# Arduino_Board.net
KiCad netlist of a schematic drawn in Altium Designer
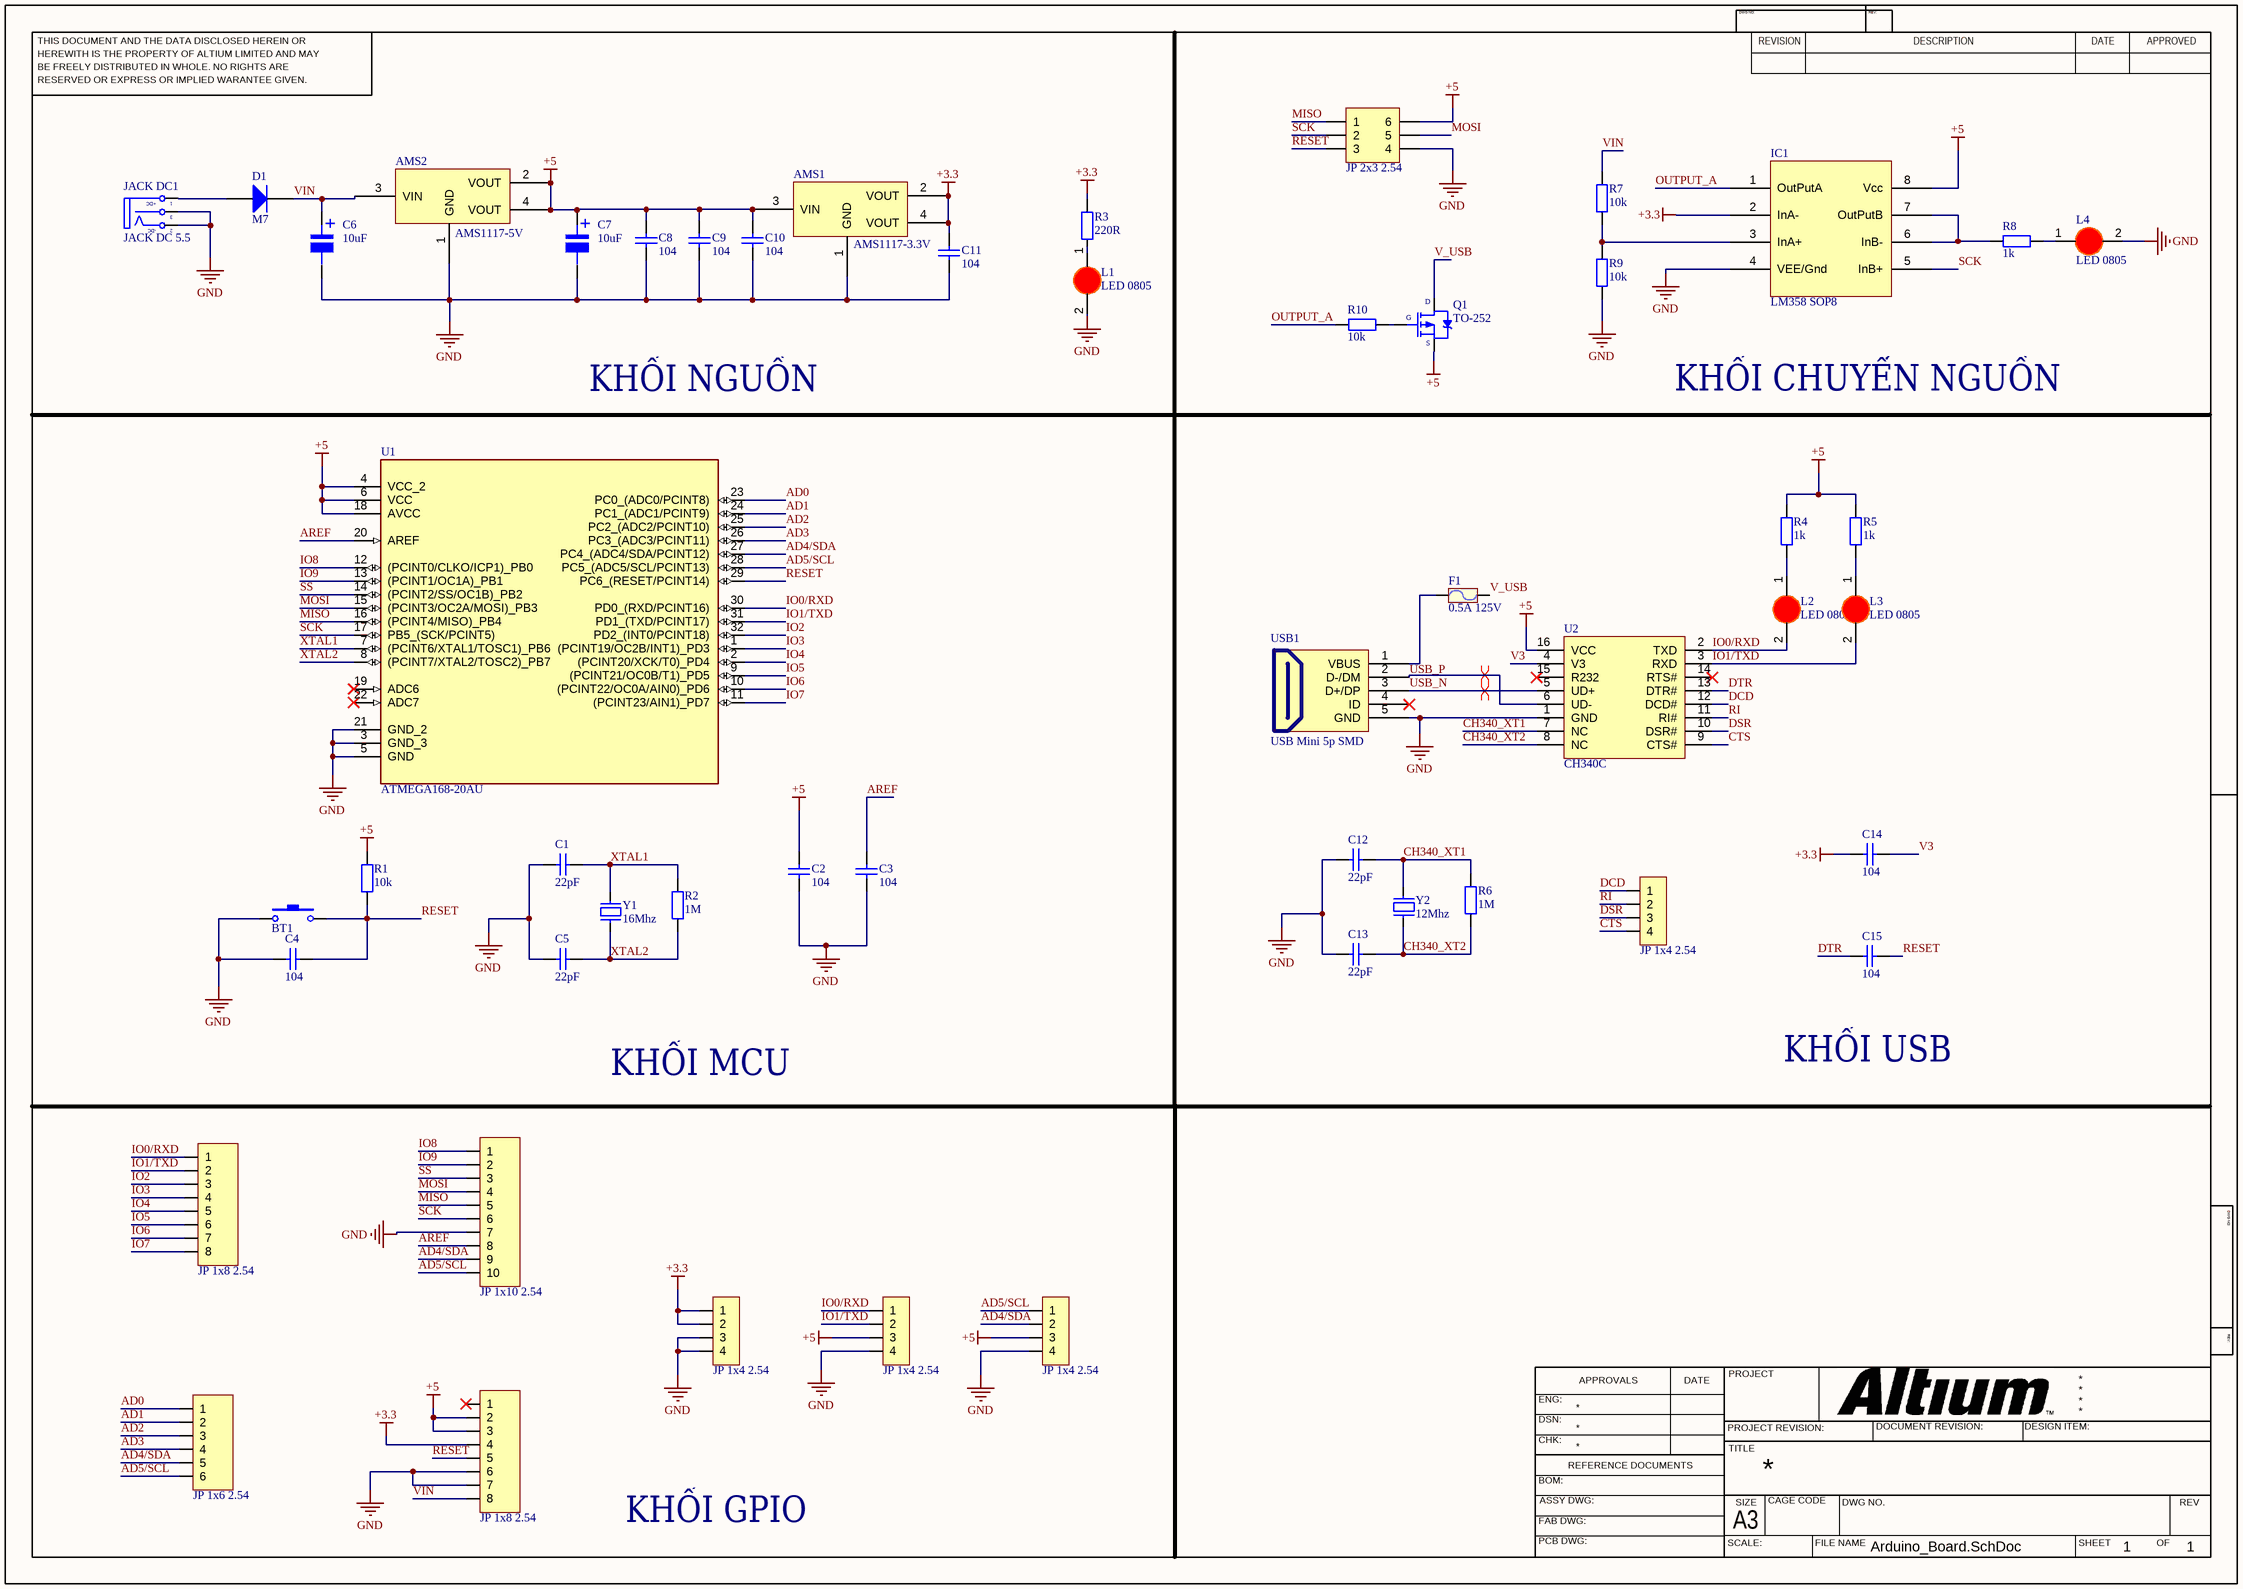
[diagram p0: Arduino_Board.SchDoc]

(export (version "E")
  (design (tool "Eeschema 10.0.6"))
  (components
    (comp (ref "AMS1")
      (value "AMS1117-3.3V")
      (footprint "SOT223")
      (description "Dán")
      (libsource (lib "Altium_Lib_by_KhueNguyenCreator") (part "AMS1117 SMD"))
    )
    (comp (ref "AMS2")
      (value "AMS1117-5V")
      (footprint "SOT223")
      (description "Dán")
      (libsource (lib "Altium_Lib_by_KhueNguyenCreator") (part "AMS1117 SMD"))
    )
    (comp (ref "BT1")
      (value "Nut Nhan 2 Chan SMD 3x6x2.5")
      (footprint "Nut Nhan 2 Chan SMD 3x6x2.5")
      (libsource (lib "Altium_Lib_by_KhueNguyenCreator") (part "Nut Nhan 2 Chan SMD 3x6x2.5"))
    )
    (comp (ref "C1")
      (value "22pF")
      (footprint "tu 0805")
      (description "Dán")
      (libsource (lib "Altium_Lib_by_KhueNguyenCreator") (part "Tu 0805 22pF 50V 10%"))
    )
    (comp (ref "C2")
      (value "104")
      (footprint "tu 0805")
      (description "Dán")
      (libsource (lib "Altium_Lib_by_KhueNguyenCreator") (part "Tu 0805 104 50V 10%"))
    )
    (comp (ref "C3")
      (value "104")
      (footprint "tu 0805")
      (description "Dán")
      (libsource (lib "Altium_Lib_by_KhueNguyenCreator") (part "Tu 0805 104 50V 10%"))
    )
    (comp (ref "C4")
      (value "104")
      (footprint "tu 0805")
      (description "Dán")
      (libsource (lib "Altium_Lib_by_KhueNguyenCreator") (part "Tu 0805 104 50V 10%"))
    )
    (comp (ref "C5")
      (value "22pF")
      (footprint "tu 0805")
      (description "Dán")
      (libsource (lib "Altium_Lib_by_KhueNguyenCreator") (part "Tu 0805 22pF 50V 10%"))
    )
    (comp (ref "C6")
      (value "10uF")
      (footprint "tu nhom 4 (b)")
      (description "Dán")
      (libsource (lib "Altium_Lib_by_KhueNguyenCreator") (part "Tu Nhom 10uF 25V"))
    )
    (comp (ref "C7")
      (value "10uF")
      (footprint "tu nhom 4 (b)")
      (description "Dán")
      (libsource (lib "Altium_Lib_by_KhueNguyenCreator") (part "Tu Nhom 10uF 25V"))
    )
    (comp (ref "C8")
      (value "104")
      (footprint "tu 0805")
      (description "Dán")
      (libsource (lib "Altium_Lib_by_KhueNguyenCreator") (part "Tu 0805 104 50V 10%"))
    )
    (comp (ref "C9")
      (value "104")
      (footprint "tu 0805")
      (description "Dán")
      (libsource (lib "Altium_Lib_by_KhueNguyenCreator") (part "Tu 0805 104 50V 10%"))
    )
    (comp (ref "C10")
      (value "104")
      (footprint "tu 0805")
      (description "Dán")
      (libsource (lib "Altium_Lib_by_KhueNguyenCreator") (part "Tu 0805 104 50V 10%"))
    )
    (comp (ref "C11")
      (value "104")
      (footprint "tu 0805")
      (description "Dán")
      (libsource (lib "Altium_Lib_by_KhueNguyenCreator") (part "Tu 0805 104 50V 10%"))
    )
    (comp (ref "C12")
      (value "22pF")
      (footprint "tu 0805")
      (description "Dán")
      (libsource (lib "Altium_Lib_by_KhueNguyenCreator") (part "Tu 0805 22pF 50V 10%"))
    )
    (comp (ref "C13")
      (value "22pF")
      (footprint "tu 0805")
      (description "Dán")
      (libsource (lib "Altium_Lib_by_KhueNguyenCreator") (part "Tu 0805 22pF 50V 10%"))
    )
    (comp (ref "C14")
      (value "104")
      (footprint "tu 0805")
      (description "Dán")
      (libsource (lib "Altium_Lib_by_KhueNguyenCreator") (part "Tu 0805 104 50V 10%"))
    )
    (comp (ref "C15")
      (value "104")
      (footprint "tu 0805")
      (description "Dán")
      (libsource (lib "Altium_Lib_by_KhueNguyenCreator") (part "Tu 0805 104 50V 10%"))
    )
    (comp (ref "D1")
      (value "M7")
      (footprint "DIODE SMA")
      (description "Dán")
      (libsource (lib "Altium_Lib_by_KhueNguyenCreator") (part "Diode M7 ( 4007 )"))
    )
    (comp (ref "F1")
      (value "0.5A 125V")
      (footprint "Cau Chi SMD1808")
      (description "Cau chi 0.5A 125V SMD1808")
      (libsource (lib "Altium_Lib_by_KhueNguyenCreator") (part "Cau chi 0.5A 125V SMD1808"))
    )
    (comp (ref "IC1")
      (value "LM358 SOP8")
      (footprint "SOP 8")
      (description "Dán")
      (libsource (lib "Altium_Lib_by_KhueNguyenCreator") (part "LM358 SOP8"))
    )
    (comp (ref "JACK DC1")
      (value "JACK DC 5.5")
      (footprint "JACK DC 5.5")
      (libsource (lib "Altium_Lib_by_KhueNguyenCreator") (part "JACK DC 5.5"))
    )
    (comp (ref "JP1")
      (value "JP 1x10 2.54")
      (footprint "JP 1x10 CT")
      (description "Cắm")
      (libsource (lib "Altium_Lib_by_KhueNguyenCreator") (part "JP 1x10 2.54 Cai Thang"))
    )
    (comp (ref "JP2")
      (value "JP 1x8 2.54")
      (footprint "JP 1x8 CT")
      (description "Cắm")
      (libsource (lib "Altium_Lib_by_KhueNguyenCreator") (part "JP 1x8 2.54 Cai Thang"))
    )
    (comp (ref "JP3")
      (value "JP 1x8 2.54")
      (footprint "JP 1x8 CT")
      (description "Cắm")
      (libsource (lib "Altium_Lib_by_KhueNguyenCreator") (part "JP 1x8 2.54 Cai Thang"))
    )
    (comp (ref "JP4")
      (value "JP 1x6 2.54")
      (footprint "JP 1x6 CT")
      (description "Cắm")
      (libsource (lib "Altium_Lib_by_KhueNguyenCreator") (part "JP 1x6 2.54 Cai Thang"))
    )
    (comp (ref "JP5")
      (value "JP 1x4 2.54")
      (footprint "JP 1x4 CT")
      (description "Cắm")
      (libsource (lib "Altium_Lib_by_KhueNguyenCreator") (part "JP 1x4 2.54 Cai Thang"))
    )
    (comp (ref "JP6")
      (value "JP 1x4 2.54")
      (footprint "JP 1x4 CT")
      (description "Cắm")
      (libsource (lib "Altium_Lib_by_KhueNguyenCreator") (part "JP 1x4 2.54 Cai Thang"))
    )
    (comp (ref "JP7")
      (value "JP 1x4 2.54")
      (footprint "JP 1x4 CT")
      (description "Cắm")
      (libsource (lib "Altium_Lib_by_KhueNguyenCreator") (part "JP 1x4 2.54 Cai Thang"))
    )
    (comp (ref "JP8")
      (value "JP 1x4 2.54")
      (footprint "JP 1x4 CT")
      (description "Cắm")
      (libsource (lib "Altium_Lib_by_KhueNguyenCreator") (part "JP 1x4 2.54 Cai Thang"))
    )
    (comp (ref "JP9")
      (value "JP 2x3 2.54")
      (footprint "JP 2x3 DT")
      (description "Cắm")
      (libsource (lib "Altium_Lib_by_KhueNguyenCreator") (part "JP 2x3 2.54 Duc Thang"))
    )
    (comp (ref "L1")
      (value "LED 0805")
      (footprint "LED-0805-Red")
      (description "Dán")
      (libsource (lib "Altium_Lib_by_KhueNguyenCreator") (part "LED 0805 Do"))
    )
    (comp (ref "L2")
      (value "LED 0805")
      (footprint "LED-0805-Red")
      (description "Dán")
      (libsource (lib "Altium_Lib_by_KhueNguyenCreator") (part "LED 0805 Do"))
    )
    (comp (ref "L3")
      (value "LED 0805")
      (footprint "LED-0805-Red")
      (description "Dán")
      (libsource (lib "Altium_Lib_by_KhueNguyenCreator") (part "LED 0805 Do"))
    )
    (comp (ref "L4")
      (value "LED 0805")
      (footprint "LED-0805-Red")
      (description "Dán")
      (libsource (lib "Altium_Lib_by_KhueNguyenCreator") (part "LED 0805 Do"))
    )
    (comp (ref "Q1")
      (value "TO-252")
      (footprint "TO-252-3_L6.6-W6.1-P4.57-LS9.9-BR-CW")
      (description "P-Channel Power MOSFET")
      (fields (field (name "PUBLISHER") "Altium Limited"))
      (libsource (lib "Altium_Lib_by_KhueNguyenCreator") (part "FET AO D409"))
    )
    (comp (ref "R1")
      (value "10k")
      (footprint "tro smd 0805")
      (description "Dán")
      (libsource (lib "Altium_Lib_by_KhueNguyenCreator") (part "Tro 0805 1% 10k"))
    )
    (comp (ref "R2")
      (value "1M")
      (footprint "tro smd 0805")
      (description "Dán")
      (libsource (lib "Altium_Lib_by_KhueNguyenCreator") (part "Tro 0805 1% 1M"))
    )
    (comp (ref "R3")
      (value "220R")
      (footprint "tro smd 0805")
      (description "Dán")
      (libsource (lib "Altium_Lib_by_KhueNguyenCreator") (part "Tro 0805 1% 200k"))
    )
    (comp (ref "R4")
      (value "1k")
      (footprint "tro smd 0805")
      (description "Dán")
      (libsource (lib "Altium_Lib_by_KhueNguyenCreator") (part "Tro 0805 1% 200k"))
    )
    (comp (ref "R5")
      (value "1k")
      (footprint "tro smd 0805")
      (description "Dán")
      (libsource (lib "Altium_Lib_by_KhueNguyenCreator") (part "Tro 0805 1% 200k"))
    )
    (comp (ref "R6")
      (value "1M")
      (footprint "tro smd 0805")
      (description "Dán")
      (libsource (lib "Altium_Lib_by_KhueNguyenCreator") (part "Tro 0805 1% 1M"))
    )
    (comp (ref "R7")
      (value "10k")
      (footprint "tro smd 0805")
      (description "Dán")
      (libsource (lib "Altium_Lib_by_KhueNguyenCreator") (part "Tro 0805 1% 10k"))
    )
    (comp (ref "R8")
      (value "1k")
      (footprint "tro smd 0805")
      (description "Dán")
      (libsource (lib "Altium_Lib_by_KhueNguyenCreator") (part "Tro 0805 1% 200k"))
    )
    (comp (ref "R9")
      (value "10k")
      (footprint "tro smd 0805")
      (description "Dán")
      (libsource (lib "Altium_Lib_by_KhueNguyenCreator") (part "Tro 0805 1% 10k"))
    )
    (comp (ref "R10")
      (value "10k")
      (footprint "tro smd 0805")
      (description "Dán")
      (libsource (lib "Altium_Lib_by_KhueNguyenCreator") (part "Tro 0805 1% 200k"))
    )
    (comp (ref "U1")
      (value "ATMEGA168-20AU")
      (footprint "ATMEGA168")
      (description "AVR AVRÂ® ATmega Microcontroller IC 8-Bit 20MHz 16KB _8K x 16_ FLASH 32-TQFP _7x7_")
      (fields (field (name "MF") "Microchip"))
      (libsource (lib "Altium_Lib_by_KhueNguyenCreator") (part "ATMEGA168-20AU"))
    )
    (comp (ref "U2")
      (value "CH340C")
      (footprint "SOIC16_50_284_25X90_SMT")
      (description "USB Bridge, USB to UART USB 2.0 UART Interface")
      (fields (field (name "MANUFACTURER") "Olimex"))
      (libsource (lib "Altium_Lib_by_KhueNguyenCreator") (part "CH340C"))
    )
    (comp (ref "USB1")
      (value "USB Mini 5p SMD")
      (footprint "USB Mini 5p SMD")
      (description "USB Type B")
      (libsource (lib "Altium_Lib_by_KhueNguyenCreator") (part "USB Mini 5p SMD"))
    )
    (comp (ref "Y1")
      (value "16Mhz")
      (footprint "Thach Anh 2 chan SMD")
      (description "Crystal For all Crystal 2pin.")
      (libsource (lib "Altium_Lib_by_KhueNguyenCreator") (part "Thach Anh 2 chan SMD"))
    )
    (comp (ref "Y2")
      (value "12Mhz")
      (footprint "Thach Anh 2 chan SMD")
      (description "Crystal For all Crystal 2pin.")
      (libsource (lib "Altium_Lib_by_KhueNguyenCreator") (part "Thach Anh 2 chan SMD"))
    )
  )
  (nets
    (net (code "1") (name "+3.3") (class "Default")
      (node (ref "AMS1") (pin "2") (pinfunction "VOUT_2") (pintype "passive"))
      (node (ref "AMS1") (pin "4") (pinfunction "VOUT_4") (pintype "passive"))
      (node (ref "C11") (pin "1") (pinfunction "1_1") (pintype "passive"))
      (node (ref "C14") (pin "1") (pinfunction "1_1") (pintype "passive"))
      (node (ref "IC1") (pin "2") (pinfunction "InA-_2") (pintype "passive"))
      (node (ref "JP3") (pin "4") (pinfunction "4_4") (pintype "passive"))
      (node (ref "JP5") (pin "1") (pinfunction "1_1") (pintype "passive"))
      (node (ref "JP5") (pin "2") (pinfunction "2_2") (pintype "passive"))
      (node (ref "R3") (pin "2") (pinfunction "2_2") (pintype "passive"))
    )
    (net (code "2") (name "+5") (class "Default")
      (node (ref "AMS1") (pin "3") (pinfunction "VIN_3") (pintype "passive"))
      (node (ref "AMS2") (pin "2") (pinfunction "VOUT_2") (pintype "passive"))
      (node (ref "AMS2") (pin "4") (pinfunction "VOUT_4") (pintype "passive"))
      (node (ref "C10") (pin "1") (pinfunction "1_1") (pintype "passive"))
      (node (ref "C2") (pin "1") (pinfunction "1_1") (pintype "passive"))
      (node (ref "C7") (pin "1") (pinfunction "1_1") (pintype "passive"))
      (node (ref "C8") (pin "1") (pinfunction "1_1") (pintype "passive"))
      (node (ref "C9") (pin "1") (pinfunction "1_1") (pintype "passive"))
      (node (ref "IC1") (pin "8") (pinfunction "Vcc_8") (pintype "passive"))
      (node (ref "JP3") (pin "2") (pinfunction "2_2") (pintype "passive"))
      (node (ref "JP3") (pin "3") (pinfunction "3_3") (pintype "passive"))
      (node (ref "JP6") (pin "3") (pinfunction "3_3") (pintype "passive"))
      (node (ref "JP7") (pin "3") (pinfunction "3_3") (pintype "passive"))
      (node (ref "JP9") (pin "6") (pinfunction "6_6") (pintype "passive"))
      (node (ref "Q1") (pin "3") (pinfunction "S_3") (pintype "passive"))
      (node (ref "R1") (pin "2") (pinfunction "2_2") (pintype "passive"))
      (node (ref "R4") (pin "2") (pinfunction "2_2") (pintype "passive"))
      (node (ref "R5") (pin "2") (pinfunction "2_2") (pintype "passive"))
      (node (ref "U1") (pin "18") (pinfunction "AVCC_18") (pintype "power_in"))
      (node (ref "U1") (pin "4") (pinfunction "VCC_2_4") (pintype "power_in"))
      (node (ref "U1") (pin "6") (pinfunction "VCC_6") (pintype "power_in"))
      (node (ref "U2") (pin "16") (pinfunction "VCC_16") (pintype "passive"))
    )
    (net (code "4") (name "/AD0") (class "Default")
      (node (ref "JP4") (pin "1") (pinfunction "1_1") (pintype "passive"))
      (node (ref "U1") (pin "23") (pinfunction "PC0_(ADC0/PCINT8)_23") (pintype "bidirectional"))
    )
    (net (code "5") (name "/AD1") (class "Default")
      (node (ref "JP4") (pin "2") (pinfunction "2_2") (pintype "passive"))
      (node (ref "U1") (pin "24") (pinfunction "PC1_(ADC1/PCINT9)_24") (pintype "bidirectional"))
    )
    (net (code "6") (name "/AD2") (class "Default")
      (node (ref "JP4") (pin "3") (pinfunction "3_3") (pintype "passive"))
      (node (ref "U1") (pin "25") (pinfunction "PC2_(ADC2/PCINT10)_25") (pintype "bidirectional"))
    )
    (net (code "7") (name "/AD3") (class "Default")
      (node (ref "JP4") (pin "4") (pinfunction "4_4") (pintype "passive"))
      (node (ref "U1") (pin "26") (pinfunction "PC3_(ADC3/PCINT11)_26") (pintype "bidirectional"))
    )
    (net (code "8") (name "/AD4{slash}SDA") (class "Default")
      (node (ref "JP1") (pin "9") (pinfunction "9_9") (pintype "passive"))
      (node (ref "JP4") (pin "5") (pinfunction "5_5") (pintype "passive"))
      (node (ref "JP7") (pin "2") (pinfunction "2_2") (pintype "passive"))
      (node (ref "U1") (pin "27") (pinfunction "PC4_(ADC4/SDA/PCINT12)_27") (pintype "bidirectional"))
    )
    (net (code "9") (name "/AD5{slash}SCL") (class "Default")
      (node (ref "JP1") (pin "10") (pinfunction "10_10") (pintype "passive"))
      (node (ref "JP4") (pin "6") (pinfunction "6_6") (pintype "passive"))
      (node (ref "JP7") (pin "1") (pinfunction "1_1") (pintype "passive"))
      (node (ref "U1") (pin "28") (pinfunction "PC5_(ADC5/SCL/PCINT13)_28") (pintype "bidirectional"))
    )
    (net (code "10") (name "/AREF") (class "Default")
      (node (ref "C3") (pin "1") (pinfunction "1_1") (pintype "passive"))
      (node (ref "JP1") (pin "8") (pinfunction "8_8") (pintype "passive"))
      (node (ref "U1") (pin "20") (pinfunction "AREF_20") (pintype "input"))
    )
    (net (code "11") (name "/CH340_XT1") (class "Default")
      (node (ref "C12") (pin "1") (pinfunction "1_1") (pintype "passive"))
      (node (ref "R6") (pin "2") (pinfunction "2_2") (pintype "passive"))
      (node (ref "U2") (pin "7") (pinfunction "NC_7") (pintype "passive"))
      (node (ref "Y2") (pin "2") (pinfunction "2_2") (pintype "passive"))
    )
    (net (code "12") (name "/CH340_XT2") (class "Default")
      (node (ref "C13") (pin "1") (pinfunction "1_1") (pintype "passive"))
      (node (ref "R6") (pin "1") (pinfunction "1_1") (pintype "passive"))
      (node (ref "U2") (pin "8") (pinfunction "NC_8") (pintype "passive"))
      (node (ref "Y2") (pin "1") (pinfunction "1_1") (pintype "passive"))
    )
    (net (code "13") (name "/CTS") (class "Default")
      (node (ref "JP8") (pin "4") (pinfunction "4_4") (pintype "passive"))
      (node (ref "U2") (pin "9") (pinfunction "CTS#_9") (pintype "passive"))
    )
    (net (code "14") (name "/DCD") (class "Default")
      (node (ref "JP8") (pin "1") (pinfunction "1_1") (pintype "passive"))
      (node (ref "U2") (pin "12") (pinfunction "DCD#_12") (pintype "passive"))
    )
    (net (code "15") (name "/DSR") (class "Default")
      (node (ref "JP8") (pin "3") (pinfunction "3_3") (pintype "passive"))
      (node (ref "U2") (pin "10") (pinfunction "DSR#_10") (pintype "passive"))
    )
    (net (code "16") (name "/DTR") (class "Default")
      (node (ref "C15") (pin "1") (pinfunction "1_1") (pintype "passive"))
      (node (ref "U2") (pin "13") (pinfunction "DTR#_13") (pintype "passive"))
    )
    (net (code "17") (name "/IO0{slash}RXD") (class "Default")
      (node (ref "JP2") (pin "1") (pinfunction "1_1") (pintype "passive"))
      (node (ref "JP6") (pin "1") (pinfunction "1_1") (pintype "passive"))
      (node (ref "L2") (pin "2") (pinfunction "K_2") (pintype "passive"))
      (node (ref "U1") (pin "30") (pinfunction "PD0_(RXD/PCINT16)_30") (pintype "bidirectional"))
      (node (ref "U2") (pin "2") (pinfunction "TXD_2") (pintype "passive"))
    )
    (net (code "18") (name "/IO1{slash}TXD") (class "Default")
      (node (ref "JP2") (pin "2") (pinfunction "2_2") (pintype "passive"))
      (node (ref "JP6") (pin "2") (pinfunction "2_2") (pintype "passive"))
      (node (ref "L3") (pin "2") (pinfunction "K_2") (pintype "passive"))
      (node (ref "U1") (pin "31") (pinfunction "PD1_(TXD/PCINT17)_31") (pintype "bidirectional"))
      (node (ref "U2") (pin "3") (pinfunction "RXD_3") (pintype "passive"))
    )
    (net (code "19") (name "/IO2") (class "Default")
      (node (ref "JP2") (pin "3") (pinfunction "3_3") (pintype "passive"))
      (node (ref "U1") (pin "32") (pinfunction "PD2_(INT0/PCINT18)_32") (pintype "bidirectional"))
    )
    (net (code "20") (name "/IO3") (class "Default")
      (node (ref "JP2") (pin "4") (pinfunction "4_4") (pintype "passive"))
      (node (ref "U1") (pin "1") (pinfunction "(PCINT19/OC2B/INT1)_PD3_1") (pintype "bidirectional"))
    )
    (net (code "21") (name "/IO4") (class "Default")
      (node (ref "JP2") (pin "5") (pinfunction "5_5") (pintype "passive"))
      (node (ref "U1") (pin "2") (pinfunction "(PCINT20/XCK/T0)_PD4_2") (pintype "bidirectional"))
    )
    (net (code "22") (name "/IO5") (class "Default")
      (node (ref "JP2") (pin "6") (pinfunction "6_6") (pintype "passive"))
      (node (ref "U1") (pin "9") (pinfunction "(PCINT21/OC0B/T1)_PD5_9") (pintype "bidirectional"))
    )
    (net (code "23") (name "/IO6") (class "Default")
      (node (ref "JP2") (pin "7") (pinfunction "7_7") (pintype "passive"))
      (node (ref "U1") (pin "10") (pinfunction "(PCINT22/OC0A/AIN0)_PD6_10") (pintype "bidirectional"))
    )
    (net (code "24") (name "/IO7") (class "Default")
      (node (ref "JP2") (pin "8") (pinfunction "8_8") (pintype "passive"))
      (node (ref "U1") (pin "11") (pinfunction "(PCINT23/AIN1)_PD7_11") (pintype "bidirectional"))
    )
    (net (code "25") (name "/IO8") (class "Default")
      (node (ref "JP1") (pin "1") (pinfunction "1_1") (pintype "passive"))
      (node (ref "U1") (pin "12") (pinfunction "(PCINT0/CLKO/ICP1)_PB0_12") (pintype "bidirectional"))
    )
    (net (code "26") (name "/IO9") (class "Default")
      (node (ref "JP1") (pin "2") (pinfunction "2_2") (pintype "passive"))
      (node (ref "U1") (pin "13") (pinfunction "(PCINT1/OC1A)_PB1_13") (pintype "bidirectional"))
    )
    (net (code "27") (name "/MISO") (class "Default")
      (node (ref "JP1") (pin "5") (pinfunction "5_5") (pintype "passive"))
      (node (ref "JP9") (pin "1") (pinfunction "1_1") (pintype "passive"))
      (node (ref "U1") (pin "16") (pinfunction "(PCINT4/MISO)_PB4_16") (pintype "bidirectional"))
    )
    (net (code "28") (name "/MOSI") (class "Default")
      (node (ref "JP1") (pin "4") (pinfunction "4_4") (pintype "passive"))
      (node (ref "JP9") (pin "5") (pinfunction "5_5") (pintype "passive"))
      (node (ref "U1") (pin "15") (pinfunction "(PCINT3/OC2A/MOSI)_PB3_15") (pintype "bidirectional"))
    )
    (net (code "29") (name "/OUTPUT_A") (class "Default")
      (node (ref "IC1") (pin "1") (pinfunction "OutPutA_1") (pintype "passive"))
      (node (ref "R10") (pin "2") (pinfunction "2_2") (pintype "passive"))
    )
    (net (code "30") (name "/RESET") (class "Default")
      (node (ref "BT1") (pin "2") (pinfunction "2_2") (pintype "passive"))
      (node (ref "C15") (pin "2") (pinfunction "2_2") (pintype "passive"))
      (node (ref "C4") (pin "1") (pinfunction "1_1") (pintype "passive"))
      (node (ref "JP3") (pin "5") (pinfunction "5_5") (pintype "passive"))
      (node (ref "JP9") (pin "3") (pinfunction "3_3") (pintype "passive"))
      (node (ref "R1") (pin "1") (pinfunction "1_1") (pintype "passive"))
      (node (ref "U1") (pin "29") (pinfunction "PC6_(RESET/PCINT14)_29") (pintype "bidirectional"))
    )
    (net (code "31") (name "/RI") (class "Default")
      (node (ref "JP8") (pin "2") (pinfunction "2_2") (pintype "passive"))
      (node (ref "U2") (pin "11") (pinfunction "RI#_11") (pintype "passive"))
    )
    (net (code "32") (name "/SCK") (class "Default")
      (node (ref "IC1") (pin "5") (pinfunction "InB+_5") (pintype "passive"))
      (node (ref "JP1") (pin "6") (pinfunction "6_6") (pintype "passive"))
      (node (ref "JP9") (pin "2") (pinfunction "2_2") (pintype "passive"))
      (node (ref "U1") (pin "17") (pinfunction "PB5_(SCK/PCINT5)_17") (pintype "bidirectional"))
    )
    (net (code "33") (name "/SS") (class "Default")
      (node (ref "JP1") (pin "3") (pinfunction "3_3") (pintype "passive"))
      (node (ref "U1") (pin "14") (pinfunction "(PCINT2/SS/OC1B)_PB2_14") (pintype "bidirectional"))
    )
    (net (code "34") (name "/USB_N") (class "Default")
      (node (ref "U2") (pin "5") (pinfunction "UD+_5") (pintype "passive"))
      (node (ref "USB1") (pin "3") (pinfunction "D+/DP_3") (pintype "passive"))
    )
    (net (code "35") (name "/USB_P") (class "Default")
      (node (ref "U2") (pin "6") (pinfunction "UD-_6") (pintype "passive"))
      (node (ref "USB1") (pin "2") (pinfunction "D-/DM_2") (pintype "passive"))
    )
    (net (code "36") (name "/V3") (class "Default")
      (node (ref "C14") (pin "2") (pinfunction "2_2") (pintype "passive"))
      (node (ref "U2") (pin "4") (pinfunction "V3_4") (pintype "passive"))
    )
    (net (code "37") (name "/VIN") (class "Default")
      (node (ref "AMS2") (pin "3") (pinfunction "VIN_3") (pintype "passive"))
      (node (ref "C6") (pin "1") (pinfunction "1_1") (pintype "passive"))
      (node (ref "D1") (pin "2") (pinfunction "K_2") (pintype "passive"))
      (node (ref "JP3") (pin "8") (pinfunction "8_8") (pintype "passive"))
      (node (ref "R7") (pin "2") (pinfunction "2_2") (pintype "passive"))
    )
    (net (code "38") (name "/V_USB") (class "Default")
      (node (ref "F1") (pin "2") (pinfunction "2_2") (pintype "passive"))
      (node (ref "Q1") (pin "2") (pinfunction "D_2") (pintype "passive"))
    )
    (net (code "39") (name "/XTAL1") (class "Default")
      (node (ref "C1") (pin "1") (pinfunction "1_1") (pintype "passive"))
      (node (ref "R2") (pin "2") (pinfunction "2_2") (pintype "passive"))
      (node (ref "U1") (pin "7") (pinfunction "(PCINT6/XTAL1/TOSC1)_PB6_7") (pintype "bidirectional"))
      (node (ref "Y1") (pin "2") (pinfunction "2_2") (pintype "passive"))
    )
    (net (code "40") (name "/XTAL2") (class "Default")
      (node (ref "C5") (pin "1") (pinfunction "1_1") (pintype "passive"))
      (node (ref "R2") (pin "1") (pinfunction "1_1") (pintype "passive"))
      (node (ref "U1") (pin "8") (pinfunction "(PCINT7/XTAL2/TOSC2)_PB7_8") (pintype "bidirectional"))
      (node (ref "Y1") (pin "1") (pinfunction "1_1") (pintype "passive"))
    )
    (net (code "41") (name "GND") (class "Default")
      (node (ref "AMS1") (pin "1") (pinfunction "GND_1") (pintype "passive"))
      (node (ref "AMS2") (pin "1") (pinfunction "GND_1") (pintype "passive"))
      (node (ref "BT1") (pin "1") (pinfunction "1_1") (pintype "passive"))
      (node (ref "C1") (pin "2") (pinfunction "2_2") (pintype "passive"))
      (node (ref "C10") (pin "2") (pinfunction "2_2") (pintype "passive"))
      (node (ref "C11") (pin "2") (pinfunction "2_2") (pintype "passive"))
      (node (ref "C12") (pin "2") (pinfunction "2_2") (pintype "passive"))
      (node (ref "C13") (pin "2") (pinfunction "2_2") (pintype "passive"))
      (node (ref "C2") (pin "2") (pinfunction "2_2") (pintype "passive"))
      (node (ref "C3") (pin "2") (pinfunction "2_2") (pintype "passive"))
      (node (ref "C4") (pin "2") (pinfunction "2_2") (pintype "passive"))
      (node (ref "C5") (pin "2") (pinfunction "2_2") (pintype "passive"))
      (node (ref "C6") (pin "2") (pinfunction "2_2") (pintype "passive"))
      (node (ref "C7") (pin "2") (pinfunction "2_2") (pintype "passive"))
      (node (ref "C8") (pin "2") (pinfunction "2_2") (pintype "passive"))
      (node (ref "C9") (pin "2") (pinfunction "2_2") (pintype "passive"))
      (node (ref "IC1") (pin "4") (pinfunction "VEE/Gnd_4") (pintype "passive"))
      (node (ref "JACK DC1") (pin "2") (pinfunction "TN_2") (pintype "passive"))
      (node (ref "JACK DC1") (pin "3") (pinfunction "S_3") (pintype "power_in"))
      (node (ref "JP1") (pin "7") (pinfunction "7_7") (pintype "passive"))
      (node (ref "JP3") (pin "6") (pinfunction "6_6") (pintype "passive"))
      (node (ref "JP3") (pin "7") (pinfunction "7_7") (pintype "passive"))
      (node (ref "JP5") (pin "3") (pinfunction "3_3") (pintype "passive"))
      (node (ref "JP5") (pin "4") (pinfunction "4_4") (pintype "passive"))
      (node (ref "JP6") (pin "4") (pinfunction "4_4") (pintype "passive"))
      (node (ref "JP7") (pin "4") (pinfunction "4_4") (pintype "passive"))
      (node (ref "JP9") (pin "4") (pinfunction "4_4") (pintype "passive"))
      (node (ref "L1") (pin "2") (pinfunction "K_2") (pintype "passive"))
      (node (ref "L4") (pin "2") (pinfunction "K_2") (pintype "passive"))
      (node (ref "R9") (pin "1") (pinfunction "1_1") (pintype "passive"))
      (node (ref "U1") (pin "21") (pinfunction "GND_2_21") (pintype "passive"))
      (node (ref "U1") (pin "3") (pinfunction "GND_3_3") (pintype "passive"))
      (node (ref "U1") (pin "5") (pinfunction "GND_5") (pintype "passive"))
      (node (ref "U2") (pin "1") (pinfunction "GND_1") (pintype "passive"))
      (node (ref "USB1") (pin "5") (pinfunction "GND_5") (pintype "passive"))
    )
    (net (code "42") (name "Net-(D1-A)") (class "Default")
      (node (ref "D1") (pin "1") (pinfunction "A_1") (pintype "passive"))
      (node (ref "JACK DC1") (pin "1") (pinfunction "T_1") (pintype "passive"))
    )
    (net (code "43") (name "Net-(IC1-InA+)") (class "Default")
      (node (ref "IC1") (pin "3") (pinfunction "InA+_3") (pintype "passive"))
      (node (ref "R7") (pin "1") (pinfunction "1_1") (pintype "passive"))
      (node (ref "R9") (pin "2") (pinfunction "2_2") (pintype "passive"))
    )
    (net (code "44") (name "Net-(IC1-InB-)") (class "Default")
      (node (ref "IC1") (pin "6") (pinfunction "InB-_6") (pintype "passive"))
      (node (ref "IC1") (pin "7") (pinfunction "OutPutB_7") (pintype "passive"))
      (node (ref "R8") (pin "2") (pinfunction "2_2") (pintype "passive"))
    )
    (net (code "45") (name "Net-(L1-A)") (class "Default")
      (node (ref "L1") (pin "1") (pinfunction "A_1") (pintype "passive"))
      (node (ref "R3") (pin "1") (pinfunction "1_1") (pintype "passive"))
    )
    (net (code "46") (name "Net-(L2-A)") (class "Default")
      (node (ref "L2") (pin "1") (pinfunction "A_1") (pintype "passive"))
      (node (ref "R4") (pin "1") (pinfunction "1_1") (pintype "passive"))
    )
    (net (code "47") (name "Net-(L3-A)") (class "Default")
      (node (ref "L3") (pin "1") (pinfunction "A_1") (pintype "passive"))
      (node (ref "R5") (pin "1") (pinfunction "1_1") (pintype "passive"))
    )
    (net (code "48") (name "Net-(L4-A)") (class "Default")
      (node (ref "L4") (pin "1") (pinfunction "A_1") (pintype "passive"))
      (node (ref "R8") (pin "1") (pinfunction "1_1") (pintype "passive"))
    )
    (net (code "49") (name "Net-(Q1-G)") (class "Default")
      (node (ref "Q1") (pin "1") (pinfunction "G_1") (pintype "passive"))
      (node (ref "R10") (pin "1") (pinfunction "1_1") (pintype "passive"))
    )
    (net (code "50") (name "Net-(USB1-VBUS)") (class "Default")
      (node (ref "F1") (pin "1") (pinfunction "1_1") (pintype "passive"))
      (node (ref "USB1") (pin "1") (pinfunction "VBUS_1") (pintype "passive"))
    )
    (net (code "51") (name "unconnected-(JP3-Pad1)") (class "Default")
      (node (ref "JP3") (pin "1") (pinfunction "1_1") (pintype "passive+no_connect"))
    )
    (net (code "52") (name "unconnected-(U1-ADC6-Pad19)") (class "Default")
      (node (ref "U1") (pin "19") (pinfunction "ADC6_19") (pintype "input+no_connect"))
    )
    (net (code "53") (name "unconnected-(U1-ADC7-Pad22)") (class "Default")
      (node (ref "U1") (pin "22") (pinfunction "ADC7_22") (pintype "input+no_connect"))
    )
    (net (code "54") (name "unconnected-(U2-R232-Pad15)") (class "Default")
      (node (ref "U2") (pin "15") (pinfunction "R232_15") (pintype "passive+no_connect"))
    )
    (net (code "55") (name "unconnected-(U2-RTS#-Pad14)") (class "Default")
      (node (ref "U2") (pin "14") (pinfunction "RTS#_14") (pintype "passive+no_connect"))
    )
    (net (code "56") (name "unconnected-(USB1-ID-Pad4)") (class "Default")
      (node (ref "USB1") (pin "4") (pinfunction "ID_4") (pintype "passive+no_connect"))
    )
  )
)
